# sata_m2.net
KiCad netlist of a schematic drawn in Altium Designer
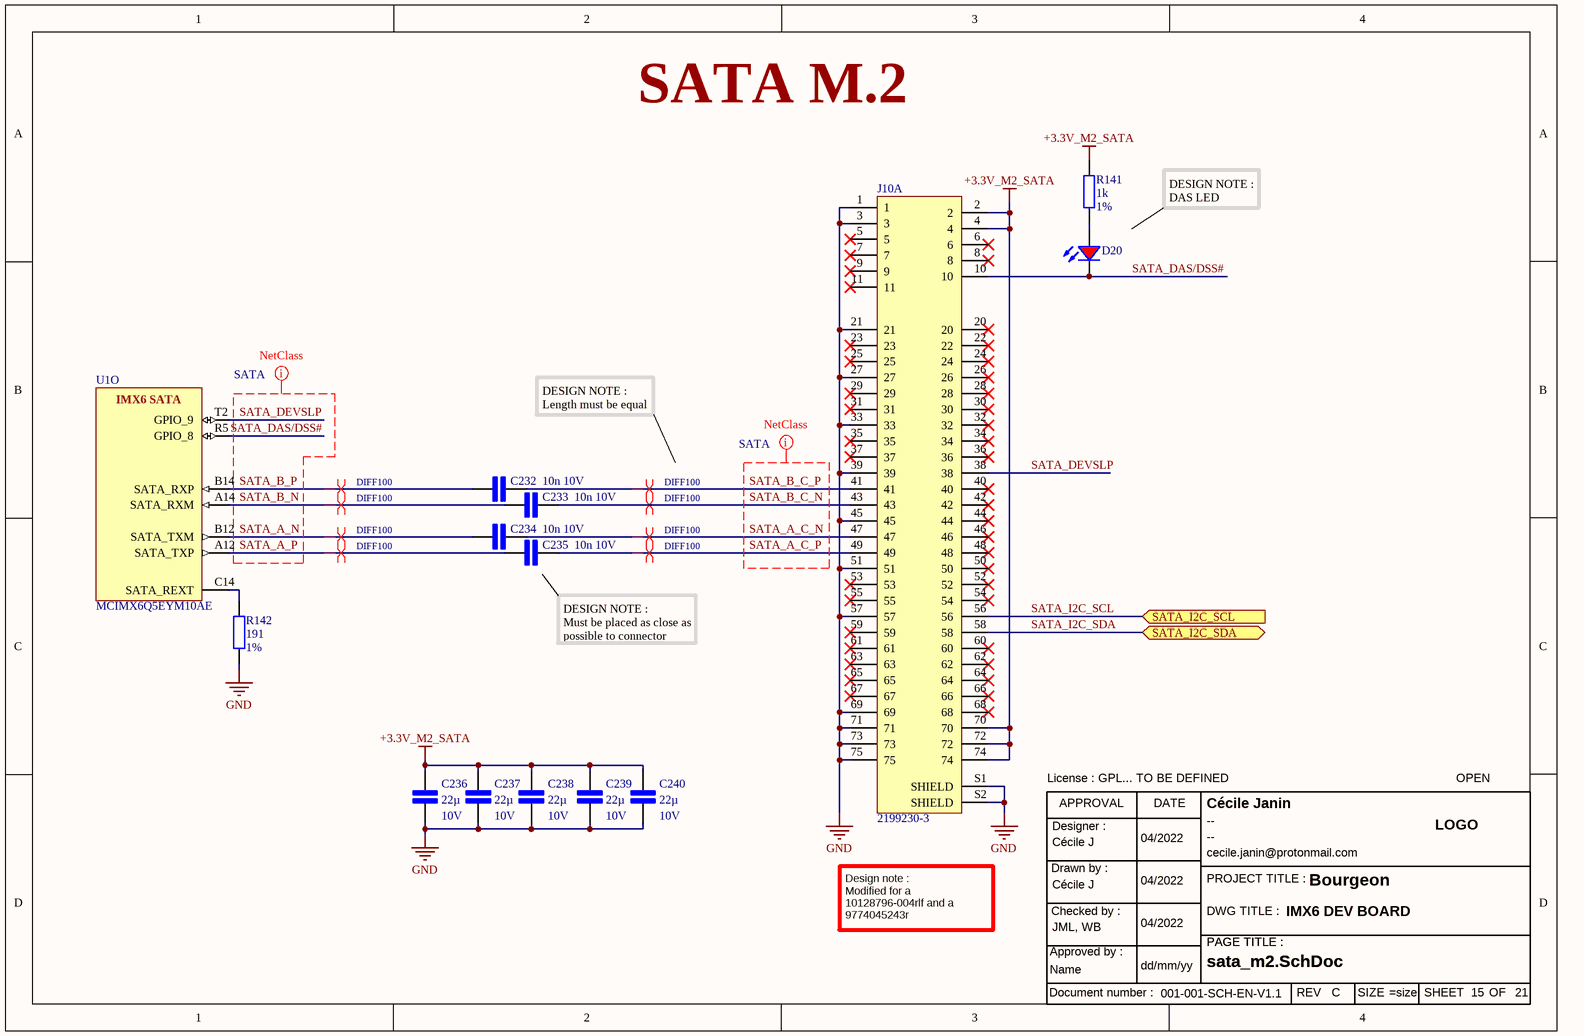
[diagram p0: sata_m2.SchDoc]

(export (version "E")
  (design (tool "Eeschema 10.0.6"))
  (components
    (comp (ref "C232")
      (value "10n")
      (footprint "CAP CER 0201/0603")
      (description "cap ceramique 10n 10V 10% 0201")
      (fields (field (name "TENSION DU DIÉLECTRIQUE") "10V"))
      (libsource (lib "First Board IMX6") (part "cap 10n 10V"))
    )
    (comp (ref "C233")
      (value "10n")
      (footprint "CAP CER 0201/0603")
      (description "cap ceramique 10n 10V 10% 0201")
      (fields (field (name "TENSION DU DIÉLECTRIQUE") "10V"))
      (libsource (lib "First Board IMX6") (part "cap 10n 10V"))
    )
    (comp (ref "C234")
      (value "10n")
      (footprint "CAP CER 0201/0603")
      (description "cap ceramique 10n 10V 10% 0201")
      (fields (field (name "TENSION DU DIÉLECTRIQUE") "10V"))
      (libsource (lib "First Board IMX6") (part "cap 10n 10V"))
    )
    (comp (ref "C235")
      (value "10n")
      (footprint "CAP CER 0201/0603")
      (description "cap ceramique 10n 10V 10% 0201")
      (fields (field (name "TENSION DU DIÉLECTRIQUE") "10V"))
      (libsource (lib "First Board IMX6") (part "cap 10n 10V"))
    )
    (comp (ref "C236")
      (value "22µ")
      (footprint "Cap cer 0603/4608")
      (description "cap cer 22µ 10V 10% X5R 0603")
      (fields (field (name "TENSION DU DIÉLECTRIQUE") "10V"))
      (libsource (lib "First Board IMX6") (part "cap 22µ 10V"))
    )
    (comp (ref "C237")
      (value "22µ")
      (footprint "Cap cer 0603/4608")
      (description "cap cer 22µ 10V 10% X5R 0603")
      (fields (field (name "TENSION DU DIÉLECTRIQUE") "10V"))
      (libsource (lib "First Board IMX6") (part "cap 22µ 10V"))
    )
    (comp (ref "C238")
      (value "22µ")
      (footprint "Cap cer 0603/4608")
      (description "cap cer 22µ 10V 10% X5R 0603")
      (fields (field (name "TENSION DU DIÉLECTRIQUE") "10V"))
      (libsource (lib "First Board IMX6") (part "cap 22µ 10V"))
    )
    (comp (ref "C239")
      (value "22µ")
      (footprint "Cap cer 0603/4608")
      (description "cap cer 22µ 10V 10% X5R 0603")
      (fields (field (name "TENSION DU DIÉLECTRIQUE") "10V"))
      (libsource (lib "First Board IMX6") (part "cap 22µ 10V"))
    )
    (comp (ref "C240")
      (value "22µ")
      (footprint "Cap cer 0603/4608")
      (description "cap cer 22µ 10V 10% X5R 0603")
      (fields (field (name "TENSION DU DIÉLECTRIQUE") "10V"))
      (libsource (lib "First Board IMX6") (part "cap 22µ 10V"))
    )
    (comp (ref "D20")
      (value "Red, 2V, 120deg")
      (footprint "LED red 0603")
      (description "WL-SMCC SMD Mono-color Chip LED Compact, size 0603, Red, 2V, 120deg 150060RS73220")
      (fields (field (name "PART NUMBER") "150060RS73220") (field (name "PUBLISHER") "Wurth Elektronik"))
      (libsource (lib "First Board IMX6") (part "LED Red 0603"))
    )
    (comp (ref "J10")
      (value "2199230-3")
      (footprint "SATA_M2_ 2199230-3")
      (libsource (lib "First Board IMX6") (part "SATA_M.2_2199230-3 / multi interface"))
    )
    (comp (ref "R141")
      (value "1k")
      (footprint "Res 0402/1005")
      (description "res 1k 1% 0402")
      (fields (field (name "POURCENTAGE") "1%"))
      (libsource (lib "First Board IMX6") (part "res 1k 1%"))
    )
    (comp (ref "R142")
      (value "191")
      (footprint "Res 0402/1005")
      (description "res 191 ohm 1% 0402")
      (fields (field (name "POURCENTAGE") "1%"))
      (libsource (lib "First Board IMX6") (part "res 191 1%"))
    )
    (comp (ref "TB14")
      (value "Title bloc ANSI modified")
      (libsource (lib "First Board IMX6") (part "Title bloc ANSI"))
    )
    (comp (ref "U1")
      (value "MCIMX6Q5EYM10AE")
      (footprint "FRES-2197-01")
      (fields
        (field (name "PARTNUMBER") "MCIMX6Q5EYM10ACR")
        (field (name "MANUFACTURER") "Freescale Semiconductor")
      )
      (libsource (lib "First Board IMX6") (part "IMX6Q5EYM10AE"))
    )
  )
  (nets
    (net (code "1") (name "+3.3V_M2_SATA") (class "Default")
      (node (ref "C236") (pin "1") (pinfunction "3_1") (pintype "passive"))
      (node (ref "C237") (pin "1") (pinfunction "3_1") (pintype "passive"))
      (node (ref "C238") (pin "1") (pinfunction "3_1") (pintype "passive"))
      (node (ref "C239") (pin "1") (pinfunction "3_1") (pintype "passive"))
      (node (ref "C240") (pin "1") (pinfunction "3_1") (pintype "passive"))
      (node (ref "J10") (pin "2") (pinfunction "2_2") (pintype "passive"))
      (node (ref "J10") (pin "4") (pinfunction "4_4") (pintype "passive"))
      (node (ref "J10") (pin "70") (pinfunction "70_70") (pintype "passive"))
      (node (ref "J10") (pin "72") (pinfunction "72_72") (pintype "passive"))
      (node (ref "J10") (pin "74") (pinfunction "74_74") (pintype "passive"))
      (node (ref "R141") (pin "2") (pintype "passive"))
    )
    (net (code "2") (name "/SATA_A_C_N") (class "Default")
      (node (ref "C234") (pin "2") (pinfunction "4_2") (pintype "passive"))
      (node (ref "J10") (pin "47") (pinfunction "47_47") (pintype "passive"))
    )
    (net (code "3") (name "/SATA_A_C_P") (class "Default")
      (node (ref "C235") (pin "2") (pinfunction "4_2") (pintype "passive"))
      (node (ref "J10") (pin "49") (pinfunction "49_49") (pintype "passive"))
    )
    (net (code "4") (name "/SATA_A_N") (class "Default")
      (node (ref "C234") (pin "1") (pinfunction "3_1") (pintype "passive"))
      (node (ref "U1") (pin "B12") (pinfunction "SATA_TXM_B12") (pintype "output"))
    )
    (net (code "5") (name "/SATA_A_P") (class "Default")
      (node (ref "C235") (pin "1") (pinfunction "3_1") (pintype "passive"))
      (node (ref "U1") (pin "A12") (pinfunction "SATA_TXP_A12") (pintype "output"))
    )
    (net (code "6") (name "/SATA_B_C_N") (class "Default")
      (node (ref "C233") (pin "2") (pinfunction "4_2") (pintype "passive"))
      (node (ref "J10") (pin "43") (pinfunction "43_43") (pintype "passive"))
    )
    (net (code "7") (name "/SATA_B_C_P") (class "Default")
      (node (ref "C232") (pin "2") (pinfunction "4_2") (pintype "passive"))
      (node (ref "J10") (pin "41") (pinfunction "41_41") (pintype "passive"))
    )
    (net (code "8") (name "/SATA_B_N") (class "Default")
      (node (ref "C233") (pin "1") (pinfunction "3_1") (pintype "passive"))
      (node (ref "U1") (pin "A14") (pinfunction "SATA_RXM_A14") (pintype "input"))
    )
    (net (code "9") (name "/SATA_B_P") (class "Default")
      (node (ref "C232") (pin "1") (pinfunction "3_1") (pintype "passive"))
      (node (ref "U1") (pin "B14") (pinfunction "SATA_RXP_B14") (pintype "input"))
    )
    (net (code "10") (name "/SATA_DAS{slash}DSS#") (class "Default")
      (node (ref "D20") (pin "1") (pinfunction "K_1") (pintype "passive"))
      (node (ref "J10") (pin "10") (pinfunction "10_10") (pintype "passive"))
      (node (ref "U1") (pin "R5") (pinfunction "GPIO_8_R5") (pintype "bidirectional"))
    )
    (net (code "11") (name "/SATA_DEVSLP") (class "Default")
      (node (ref "J10") (pin "38") (pinfunction "38_38") (pintype "passive"))
      (node (ref "U1") (pin "T2") (pinfunction "GPIO_9_T2") (pintype "bidirectional"))
    )
    (net (code "12") (name "/SATA_I2C_SCL") (class "Default")
      (node (ref "J10") (pin "56") (pinfunction "56_56") (pintype "passive"))
    )
    (net (code "13") (name "/SATA_I2C_SDA") (class "Default")
      (node (ref "J10") (pin "58") (pinfunction "58_58") (pintype "passive"))
    )
    (net (code "14") (name "GND") (class "Default")
      (node (ref "C236") (pin "2") (pinfunction "4_2") (pintype "passive"))
      (node (ref "C237") (pin "2") (pinfunction "4_2") (pintype "passive"))
      (node (ref "C238") (pin "2") (pinfunction "4_2") (pintype "passive"))
      (node (ref "C239") (pin "2") (pinfunction "4_2") (pintype "passive"))
      (node (ref "C240") (pin "2") (pinfunction "4_2") (pintype "passive"))
      (node (ref "J10") (pin "1") (pinfunction "1_1") (pintype "passive"))
      (node (ref "J10") (pin "21") (pinfunction "21_21") (pintype "passive"))
      (node (ref "J10") (pin "27") (pinfunction "27_27") (pintype "passive"))
      (node (ref "J10") (pin "3") (pinfunction "3_3") (pintype "passive"))
      (node (ref "J10") (pin "33") (pinfunction "33_33") (pintype "passive"))
      (node (ref "J10") (pin "39") (pinfunction "39_39") (pintype "passive"))
      (node (ref "J10") (pin "45") (pinfunction "45_45") (pintype "passive"))
      (node (ref "J10") (pin "51") (pinfunction "51_51") (pintype "passive"))
      (node (ref "J10") (pin "57") (pinfunction "57_57") (pintype "passive"))
      (node (ref "J10") (pin "69") (pinfunction "69_69") (pintype "passive"))
      (node (ref "J10") (pin "71") (pinfunction "71_71") (pintype "passive"))
      (node (ref "J10") (pin "73") (pinfunction "73_73") (pintype "passive"))
      (node (ref "J10") (pin "75") (pinfunction "75_75") (pintype "passive"))
      (node (ref "J10") (pin "S1") (pinfunction "SHIELD_S1") (pintype "passive"))
      (node (ref "J10") (pin "S2") (pinfunction "SHIELD_S2") (pintype "passive"))
      (node (ref "R142") (pin "1") (pintype "passive"))
    )
    (net (code "15") (name "Net-(D20-A)") (class "Default")
      (node (ref "D20") (pin "2") (pinfunction "A_2") (pintype "passive"))
      (node (ref "R141") (pin "1") (pintype "passive"))
    )
    (net (code "16") (name "Net-(U1O-SATA_REXT)") (class "Default")
      (node (ref "R142") (pin "2") (pintype "passive"))
      (node (ref "U1") (pin "C14") (pinfunction "SATA_REXT_C14") (pintype "passive"))
    )
    (net (code "17") (name "unconnected-(J10-Pad5)") (class "Default")
      (node (ref "J10") (pin "5") (pinfunction "5_5") (pintype "passive+no_connect"))
    )
    (net (code "18") (name "unconnected-(J10-Pad6)") (class "Default")
      (node (ref "J10") (pin "6") (pinfunction "6_6") (pintype "passive+no_connect"))
    )
    (net (code "19") (name "unconnected-(J10-Pad7)") (class "Default")
      (node (ref "J10") (pin "7") (pinfunction "7_7") (pintype "passive+no_connect"))
    )
    (net (code "20") (name "unconnected-(J10-Pad8)") (class "Default")
      (node (ref "J10") (pin "8") (pinfunction "8_8") (pintype "passive+no_connect"))
    )
    (net (code "21") (name "unconnected-(J10-Pad9)") (class "Default")
      (node (ref "J10") (pin "9") (pinfunction "9_9") (pintype "passive+no_connect"))
    )
    (net (code "22") (name "unconnected-(J10-Pad11)") (class "Default")
      (node (ref "J10") (pin "11") (pinfunction "11_11") (pintype "passive+no_connect"))
    )
    (net (code "23") (name "unconnected-(J10-Pad20)") (class "Default")
      (node (ref "J10") (pin "20") (pinfunction "20_20") (pintype "passive+no_connect"))
    )
    (net (code "24") (name "unconnected-(J10-Pad22)") (class "Default")
      (node (ref "J10") (pin "22") (pinfunction "22_22") (pintype "passive+no_connect"))
    )
    (net (code "25") (name "unconnected-(J10-Pad23)") (class "Default")
      (node (ref "J10") (pin "23") (pinfunction "23_23") (pintype "passive+no_connect"))
    )
    (net (code "26") (name "unconnected-(J10-Pad24)") (class "Default")
      (node (ref "J10") (pin "24") (pinfunction "24_24") (pintype "passive+no_connect"))
    )
    (net (code "27") (name "unconnected-(J10-Pad25)") (class "Default")
      (node (ref "J10") (pin "25") (pinfunction "25_25") (pintype "passive+no_connect"))
    )
    (net (code "28") (name "unconnected-(J10-Pad26)") (class "Default")
      (node (ref "J10") (pin "26") (pinfunction "26_26") (pintype "passive+no_connect"))
    )
    (net (code "29") (name "unconnected-(J10-Pad28)") (class "Default")
      (node (ref "J10") (pin "28") (pinfunction "28_28") (pintype "passive+no_connect"))
    )
    (net (code "30") (name "unconnected-(J10-Pad29)") (class "Default")
      (node (ref "J10") (pin "29") (pinfunction "29_29") (pintype "passive+no_connect"))
    )
    (net (code "31") (name "unconnected-(J10-Pad30)") (class "Default")
      (node (ref "J10") (pin "30") (pinfunction "30_30") (pintype "passive+no_connect"))
    )
    (net (code "32") (name "unconnected-(J10-Pad31)") (class "Default")
      (node (ref "J10") (pin "31") (pinfunction "31_31") (pintype "passive+no_connect"))
    )
    (net (code "33") (name "unconnected-(J10-Pad32)") (class "Default")
      (node (ref "J10") (pin "32") (pinfunction "32_32") (pintype "passive+no_connect"))
    )
    (net (code "34") (name "unconnected-(J10-Pad34)") (class "Default")
      (node (ref "J10") (pin "34") (pinfunction "34_34") (pintype "passive+no_connect"))
    )
    (net (code "35") (name "unconnected-(J10-Pad35)") (class "Default")
      (node (ref "J10") (pin "35") (pinfunction "35_35") (pintype "passive+no_connect"))
    )
    (net (code "36") (name "unconnected-(J10-Pad36)") (class "Default")
      (node (ref "J10") (pin "36") (pinfunction "36_36") (pintype "passive+no_connect"))
    )
    (net (code "37") (name "unconnected-(J10-Pad37)") (class "Default")
      (node (ref "J10") (pin "37") (pinfunction "37_37") (pintype "passive+no_connect"))
    )
    (net (code "38") (name "unconnected-(J10-Pad40)") (class "Default")
      (node (ref "J10") (pin "40") (pinfunction "40_40") (pintype "passive+no_connect"))
    )
    (net (code "39") (name "unconnected-(J10-Pad42)") (class "Default")
      (node (ref "J10") (pin "42") (pinfunction "42_42") (pintype "passive+no_connect"))
    )
    (net (code "40") (name "unconnected-(J10-Pad44)") (class "Default")
      (node (ref "J10") (pin "44") (pinfunction "44_44") (pintype "passive+no_connect"))
    )
    (net (code "41") (name "unconnected-(J10-Pad46)") (class "Default")
      (node (ref "J10") (pin "46") (pinfunction "46_46") (pintype "passive+no_connect"))
    )
    (net (code "42") (name "unconnected-(J10-Pad48)") (class "Default")
      (node (ref "J10") (pin "48") (pinfunction "48_48") (pintype "passive+no_connect"))
    )
    (net (code "43") (name "unconnected-(J10-Pad50)") (class "Default")
      (node (ref "J10") (pin "50") (pinfunction "50_50") (pintype "passive+no_connect"))
    )
    (net (code "44") (name "unconnected-(J10-Pad52)") (class "Default")
      (node (ref "J10") (pin "52") (pinfunction "52_52") (pintype "passive+no_connect"))
    )
    (net (code "45") (name "unconnected-(J10-Pad53)") (class "Default")
      (node (ref "J10") (pin "53") (pinfunction "53_53") (pintype "passive+no_connect"))
    )
    (net (code "46") (name "unconnected-(J10-Pad54)") (class "Default")
      (node (ref "J10") (pin "54") (pinfunction "54_54") (pintype "passive+no_connect"))
    )
    (net (code "47") (name "unconnected-(J10-Pad55)") (class "Default")
      (node (ref "J10") (pin "55") (pinfunction "55_55") (pintype "passive+no_connect"))
    )
    (net (code "48") (name "unconnected-(J10-Pad59)") (class "Default")
      (node (ref "J10") (pin "59") (pinfunction "59_59") (pintype "passive+no_connect"))
    )
    (net (code "49") (name "unconnected-(J10-Pad60)") (class "Default")
      (node (ref "J10") (pin "60") (pinfunction "60_60") (pintype "passive+no_connect"))
    )
    (net (code "50") (name "unconnected-(J10-Pad61)") (class "Default")
      (node (ref "J10") (pin "61") (pinfunction "61_61") (pintype "passive+no_connect"))
    )
    (net (code "51") (name "unconnected-(J10-Pad62)") (class "Default")
      (node (ref "J10") (pin "62") (pinfunction "62_62") (pintype "passive+no_connect"))
    )
    (net (code "52") (name "unconnected-(J10-Pad63)") (class "Default")
      (node (ref "J10") (pin "63") (pinfunction "63_63") (pintype "passive+no_connect"))
    )
    (net (code "53") (name "unconnected-(J10-Pad64)") (class "Default")
      (node (ref "J10") (pin "64") (pinfunction "64_64") (pintype "passive+no_connect"))
    )
    (net (code "54") (name "unconnected-(J10-Pad65)") (class "Default")
      (node (ref "J10") (pin "65") (pinfunction "65_65") (pintype "passive+no_connect"))
    )
    (net (code "55") (name "unconnected-(J10-Pad66)") (class "Default")
      (node (ref "J10") (pin "66") (pinfunction "66_66") (pintype "passive+no_connect"))
    )
    (net (code "56") (name "unconnected-(J10-Pad67)") (class "Default")
      (node (ref "J10") (pin "67") (pinfunction "67_67") (pintype "passive+no_connect"))
    )
    (net (code "57") (name "unconnected-(J10-Pad68)") (class "Default")
      (node (ref "J10") (pin "68") (pinfunction "68_68") (pintype "passive+no_connect"))
    )
  )
)
